# MCU.net
KiCad netlist of a schematic drawn in Altium Designer
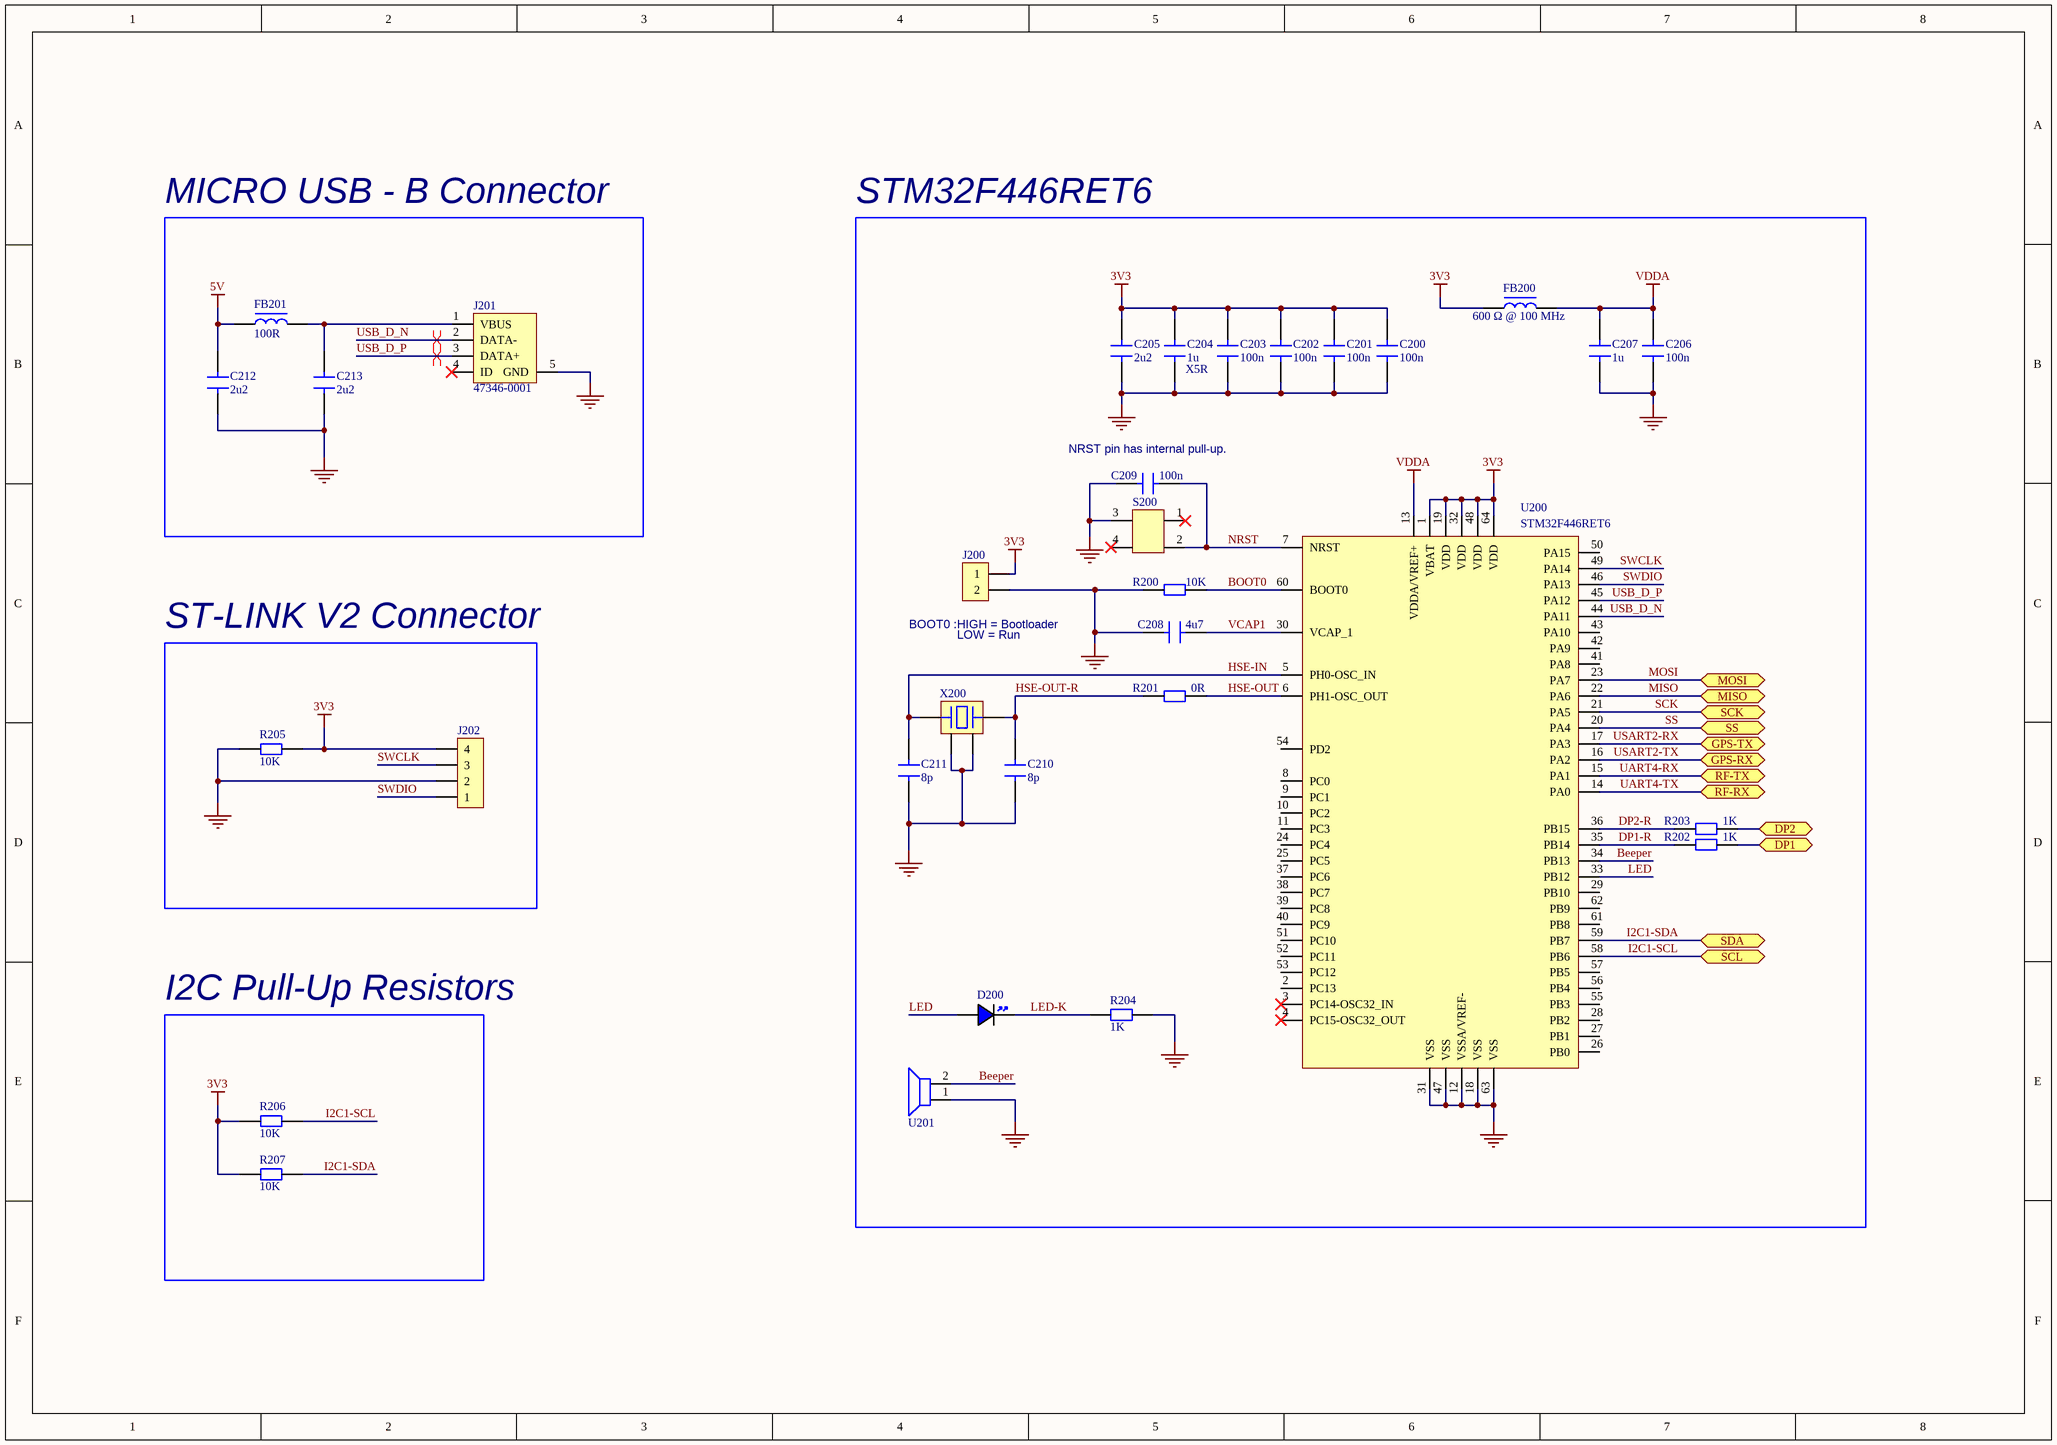
[diagram p0: MCU.SchDoc]

(export (version "E")
  (design (tool "Eeschema 10.0.6"))
  (components
    (comp (ref "C200")
      (value "100n")
      (footprint "CAP 0603")
      (description "Capacitor SMD 0603 50V")
      (libsource (lib "Schlib") (part "CAP 0603 50V"))
    )
    (comp (ref "C201")
      (value "100n")
      (footprint "CAP 0603")
      (description "Capacitor SMD 0603 50V")
      (libsource (lib "Schlib") (part "CAP 0603 50V"))
    )
    (comp (ref "C202")
      (value "100n")
      (footprint "CAP 0603")
      (description "Capacitor SMD 0603 50V")
      (libsource (lib "Schlib") (part "CAP 0603 50V"))
    )
    (comp (ref "C203")
      (value "100n")
      (footprint "CAP 0603")
      (description "Capacitor SMD 0603 50V")
      (libsource (lib "Schlib") (part "CAP 0603 50V"))
    )
    (comp (ref "C204")
      (value "1u")
      (footprint "CAP 0603")
      (description "Capacitor SMD 0603 16V")
      (libsource (lib "Schlib") (part "CAP 0603 16V"))
    )
    (comp (ref "C205")
      (value "2u2")
      (footprint "CAP 0603")
      (description "Capacitor SMD 0603 50V")
      (libsource (lib "Schlib") (part "CAP 0603 50V"))
    )
    (comp (ref "C206")
      (value "100n")
      (footprint "CAP 0603")
      (description "Capacitor SMD 0603 50V")
      (libsource (lib "Schlib") (part "CAP 0603 50V"))
    )
    (comp (ref "C207")
      (value "1u")
      (footprint "CAP 0603")
      (description "Capacitor SMD 0603 50V")
      (libsource (lib "Schlib") (part "CAP 0603 50V"))
    )
    (comp (ref "C208")
      (value "4u7")
      (footprint "CAP 0805")
      (description "Capacitor SMD 0805 25V")
      (libsource (lib "Schlib") (part "CAP 0805 25V"))
    )
    (comp (ref "C209")
      (value "100n")
      (footprint "CAP 0603")
      (description "Capacitor SMD 0603 50V")
      (libsource (lib "Schlib") (part "CAP 0603 50V"))
    )
    (comp (ref "C210")
      (value "8p")
      (footprint "CAP 0603")
      (description "Capacitor SMD 0603 50V")
      (libsource (lib "Schlib") (part "CAP 0603 50V"))
    )
    (comp (ref "C211")
      (value "8p")
      (footprint "CAP 0603")
      (description "Capacitor SMD 0603 50V")
      (libsource (lib "Schlib") (part "CAP 0603 50V"))
    )
    (comp (ref "C212")
      (value "2u2")
      (footprint "CAP 0603")
      (description "Capacitor SMD 0603 50V")
      (libsource (lib "Schlib") (part "CAP 0603 50V"))
    )
    (comp (ref "C213")
      (value "2u2")
      (footprint "CAP 0603")
      (description "Capacitor SMD 0603 50V")
      (libsource (lib "Schlib") (part "CAP 0603 50V"))
    )
    (comp (ref "D200")
      (value "LED 0805 BLUE")
      (footprint "LED 0805 BLUE")
      (description "LED 0805 GREEN SMD")
      (libsource (lib "Schlib") (part "LED 0805 BLUE"))
    )
    (comp (ref "FB200")
      (value "600 Ω @ 100 MHz")
      (footprint "FB 0603")
      (description "Ferrite Bead SMD 0603")
      (libsource (lib "Schlib") (part "FB 0603"))
    )
    (comp (ref "FB201")
      (value "100R")
      (footprint "FB 0805")
      (description "Ferrite Bead SMD 0805")
      (libsource (lib "Schlib") (part "FB 0805"))
    )
    (comp (ref "J200")
      (value "1x2 HEADER")
      (footprint "1x2 HEADER MALE")
      (libsource (lib "Schlib") (part "1x2 HEADER"))
    )
    (comp (ref "J201")
      (value "47346-0001")
      (footprint "MOLEX_47346-0001")
      (description "Micro-USB B Receptacle with Flange, Bottom Mount, Surface Mount, Lead-Free")
      (fields (field (name "MANUFACTURER") "Molex"))
      (libsource (lib "Schlib") (part "47346-0001"))
    )
    (comp (ref "J202")
      (value "1x4 HEADER MALE")
      (footprint "1X4 HEADER MALE")
      (libsource (lib "Schlib") (part "1x4 HEADER MALE"))
    )
    (comp (ref "R200")
      (value "10K")
      (footprint "RES 0603")
      (description "Resistor SMD 0603")
      (libsource (lib "Schlib") (part "RES 0603"))
    )
    (comp (ref "R201")
      (value "0R")
      (footprint "RES 0603")
      (description "Resistor SMD 0603")
      (libsource (lib "Schlib") (part "RES 0603"))
    )
    (comp (ref "R202")
      (value "1K")
      (footprint "RES 0603")
      (description "Resistor SMD 0603")
      (libsource (lib "Schlib") (part "RES 0603"))
    )
    (comp (ref "R203")
      (value "1K")
      (footprint "RES 0603")
      (description "Resistor SMD 0603")
      (libsource (lib "Schlib") (part "RES 0603"))
    )
    (comp (ref "R204")
      (value "1K")
      (footprint "RES 0603")
      (description "Resistor SMD 0603")
      (libsource (lib "Schlib") (part "RES 0603"))
    )
    (comp (ref "R205")
      (value "10K")
      (footprint "RES 0603")
      (description "Resistor SMD 0603")
      (libsource (lib "Schlib") (part "RES 0603"))
    )
    (comp (ref "R206")
      (value "10K")
      (footprint "RES 0603")
      (description "Resistor SMD 0603")
      (libsource (lib "Schlib") (part "RES 0603"))
    )
    (comp (ref "R207")
      (value "10K")
      (footprint "RES 0603")
      (description "Resistor SMD 0603")
      (libsource (lib "Schlib") (part "RES 0603"))
    )
    (comp (ref "S200")
      (value "FSM4JSMATR")
      (footprint "FSM4JSMATR")
      (description "Switch Tactile OFF (ON) SPST Round Button Gull Wing 0.05A 24VDC 1.57N SMD T/R")
      (fields (field (name "MANUFACTURER") "TE Connectivity Alcoswitch"))
      (libsource (lib "Schlib") (part "FSM4JSMATR"))
    )
    (comp (ref "U200")
      (value "STM32F446RET6")
      (footprint "STM32F446RET6")
      (description "ARM® Cortex®-M4 STM32 F4 Microcontroller IC 32-Bit 180MHz 512KB (512K x 8) FLASH 64-LQFP (10x10)")
      (fields (field (name "MANUFACTURER") "STMicroelectronics"))
      (libsource (lib "Schlib") (part "STM32F446RET6"))
    )
    (comp (ref "U201")
      (value "PS1240P02BT")
      (footprint "PS1240P02BT")
      (description "Audio Buzzer Piezo 30Vo-p 3Vo-p 70dBA Through Hole Pin Ammo")
      (fields (field (name "MANUFACTURER") "TDK"))
      (libsource (lib "Schlib") (part "PS1240P02BT"))
    )
    (comp (ref "X200")
      (value "FA-20H 16.0000MF10Z-AJ0")
      (footprint "FA-20H 16.0000MF10Z-AJ0")
      (description "Crystal 16MHz ±10ppm (Tol) ±10ppm (Stability) 8pF FUND 80Ohm 4-Pin Ultra Mini-CSMD T/R")
      (fields (field (name "MANUFACTURER") "Epson"))
      (libsource (lib "Schlib") (part "FA-20H 16.0000MF10Z-AJ0"))
    )
  )
  (nets
    (net (code "1") (name "/BOOT0") (class "Default")
      (node (ref "R200") (pin "2") (pinfunction "2_2") (pintype "passive"))
      (node (ref "U200") (pin "60") (pinfunction "BOOT0_60") (pintype "passive"))
    )
    (net (code "2") (name "/Beeper") (class "Default")
      (node (ref "U200") (pin "34") (pinfunction "PB13_34") (pintype "passive"))
      (node (ref "U201") (pin "2") (pinfunction "2_2") (pintype "passive"))
    )
    (net (code "3") (name "/DP1") (class "Default")
      (node (ref "R202") (pin "1") (pinfunction "1_1") (pintype "passive"))
    )
    (net (code "4") (name "/DP1-R") (class "Default")
      (node (ref "R202") (pin "2") (pinfunction "2_2") (pintype "passive"))
      (node (ref "U200") (pin "35") (pinfunction "PB14_35") (pintype "passive"))
    )
    (net (code "5") (name "/DP2") (class "Default")
      (node (ref "R203") (pin "2") (pinfunction "2_2") (pintype "passive"))
    )
    (net (code "6") (name "/DP2-R") (class "Default")
      (node (ref "R203") (pin "1") (pinfunction "1_1") (pintype "passive"))
      (node (ref "U200") (pin "36") (pinfunction "PB15_36") (pintype "passive"))
    )
    (net (code "7") (name "/HSE-IN") (class "Default")
      (node (ref "C211") (pin "2") (pinfunction "2_2") (pintype "passive"))
      (node (ref "U200") (pin "5") (pinfunction "PH0-OSC_IN_5") (pintype "passive"))
      (node (ref "X200") (pin "1") (pinfunction "1_1") (pintype "passive"))
    )
    (net (code "8") (name "/HSE-OUT") (class "Default")
      (node (ref "R201") (pin "2") (pinfunction "2_2") (pintype "passive"))
      (node (ref "U200") (pin "6") (pinfunction "PH1-OSC_OUT_6") (pintype "passive"))
    )
    (net (code "9") (name "/HSE-OUT-R") (class "Default")
      (node (ref "C210") (pin "2") (pinfunction "2_2") (pintype "passive"))
      (node (ref "R201") (pin "1") (pinfunction "1_1") (pintype "passive"))
      (node (ref "X200") (pin "3") (pinfunction "3_3") (pintype "passive"))
    )
    (net (code "10") (name "/I2C1-SCL") (class "Default")
      (node (ref "R206") (pin "1") (pinfunction "1_1") (pintype "passive"))
      (node (ref "U200") (pin "58") (pinfunction "PB6_58") (pintype "passive"))
    )
    (net (code "11") (name "/I2C1-SDA") (class "Default")
      (node (ref "R207") (pin "1") (pinfunction "1_1") (pintype "passive"))
      (node (ref "U200") (pin "59") (pinfunction "PB7_59") (pintype "passive"))
    )
    (net (code "12") (name "/LED") (class "Default")
      (node (ref "D200") (pin "A") (pinfunction "A_A") (pintype "passive"))
      (node (ref "U200") (pin "33") (pinfunction "PB12_33") (pintype "passive"))
    )
    (net (code "13") (name "/LED-K") (class "Default")
      (node (ref "D200") (pin "K") (pinfunction "K_K") (pintype "passive"))
      (node (ref "R204") (pin "1") (pinfunction "1_1") (pintype "passive"))
    )
    (net (code "14") (name "/MISO") (class "Default")
      (node (ref "U200") (pin "22") (pinfunction "PA6_22") (pintype "passive"))
    )
    (net (code "15") (name "/MOSI") (class "Default")
      (node (ref "U200") (pin "23") (pinfunction "PA7_23") (pintype "passive"))
    )
    (net (code "16") (name "/NRST") (class "Default")
      (node (ref "C209") (pin "2") (pinfunction "2_2") (pintype "passive"))
      (node (ref "S200") (pin "2") (pinfunction "2_2") (pintype "passive"))
      (node (ref "U200") (pin "7") (pinfunction "NRST_7") (pintype "passive"))
    )
    (net (code "17") (name "/SCK") (class "Default")
      (node (ref "U200") (pin "21") (pinfunction "PA5_21") (pintype "passive"))
    )
    (net (code "18") (name "/SS") (class "Default")
      (node (ref "U200") (pin "20") (pinfunction "PA4_20") (pintype "passive"))
    )
    (net (code "19") (name "/SWCLK") (class "Default")
      (node (ref "J202") (pin "3") (pinfunction "3_3") (pintype "passive"))
      (node (ref "U200") (pin "49") (pinfunction "PA14_49") (pintype "passive"))
    )
    (net (code "20") (name "/SWDIO") (class "Default")
      (node (ref "J202") (pin "1") (pinfunction "1_1") (pintype "passive"))
      (node (ref "U200") (pin "46") (pinfunction "PA13_46") (pintype "passive"))
    )
    (net (code "21") (name "/UART4-RX") (class "Default")
      (node (ref "U200") (pin "15") (pinfunction "PA1_15") (pintype "passive"))
    )
    (net (code "22") (name "/UART4-TX") (class "Default")
      (node (ref "U200") (pin "14") (pinfunction "PA0_14") (pintype "passive"))
    )
    (net (code "23") (name "/USART2-RX") (class "Default")
      (node (ref "U200") (pin "17") (pinfunction "PA3_17") (pintype "passive"))
    )
    (net (code "24") (name "/USART2-TX") (class "Default")
      (node (ref "U200") (pin "16") (pinfunction "PA2_16") (pintype "passive"))
    )
    (net (code "25") (name "/USB_D_N") (class "Default")
      (node (ref "J201") (pin "2") (pinfunction "DATA-_2") (pintype "passive"))
      (node (ref "U200") (pin "44") (pinfunction "PA11_44") (pintype "passive"))
    )
    (net (code "26") (name "/USB_D_P") (class "Default")
      (node (ref "J201") (pin "3") (pinfunction "DATA+_3") (pintype "passive"))
      (node (ref "U200") (pin "45") (pinfunction "PA12_45") (pintype "passive"))
    )
    (net (code "27") (name "/VCAP1") (class "Default")
      (node (ref "C208") (pin "2") (pinfunction "2_2") (pintype "passive"))
      (node (ref "U200") (pin "30") (pinfunction "VCAP_1_30") (pintype "passive"))
    )
    (net (code "28") (name "3V3") (class "Default")
      (node (ref "C200") (pin "2") (pinfunction "2_2") (pintype "passive"))
      (node (ref "C201") (pin "2") (pinfunction "2_2") (pintype "passive"))
      (node (ref "C202") (pin "2") (pinfunction "2_2") (pintype "passive"))
      (node (ref "C203") (pin "2") (pinfunction "2_2") (pintype "passive"))
      (node (ref "C204") (pin "2") (pinfunction "2_2") (pintype "passive"))
      (node (ref "C205") (pin "2") (pinfunction "2_2") (pintype "passive"))
      (node (ref "FB200") (pin "1") (pintype "passive"))
      (node (ref "J200") (pin "1") (pinfunction "1_1") (pintype "passive"))
      (node (ref "J202") (pin "4") (pinfunction "4_4") (pintype "passive"))
      (node (ref "R205") (pin "2") (pinfunction "2_2") (pintype "passive"))
      (node (ref "R206") (pin "2") (pinfunction "2_2") (pintype "passive"))
      (node (ref "R207") (pin "2") (pinfunction "2_2") (pintype "passive"))
      (node (ref "U200") (pin "1") (pinfunction "VBAT_1") (pintype "passive"))
      (node (ref "U200") (pin "19") (pinfunction "VDD_19") (pintype "passive"))
      (node (ref "U200") (pin "32") (pinfunction "VDD_32") (pintype "passive"))
      (node (ref "U200") (pin "48") (pinfunction "VDD_48") (pintype "passive"))
      (node (ref "U200") (pin "64") (pinfunction "VDD_64") (pintype "passive"))
    )
    (net (code "29") (name "5V") (class "Default")
      (node (ref "C212") (pin "1") (pinfunction "1_1") (pintype "passive"))
      (node (ref "FB201") (pin "1") (pintype "passive"))
    )
    (net (code "30") (name "GND") (class "Default")
      (node (ref "C200") (pin "1") (pinfunction "1_1") (pintype "passive"))
      (node (ref "C201") (pin "1") (pinfunction "1_1") (pintype "passive"))
      (node (ref "C202") (pin "1") (pinfunction "1_1") (pintype "passive"))
      (node (ref "C203") (pin "1") (pinfunction "1_1") (pintype "passive"))
      (node (ref "C204") (pin "1") (pinfunction "1_1") (pintype "passive"))
      (node (ref "C205") (pin "1") (pinfunction "1_1") (pintype "passive"))
      (node (ref "C206") (pin "1") (pinfunction "1_1") (pintype "passive"))
      (node (ref "C207") (pin "1") (pinfunction "1_1") (pintype "passive"))
      (node (ref "C208") (pin "1") (pinfunction "1_1") (pintype "passive"))
      (node (ref "C209") (pin "1") (pinfunction "1_1") (pintype "passive"))
      (node (ref "C210") (pin "1") (pinfunction "1_1") (pintype "passive"))
      (node (ref "C211") (pin "1") (pinfunction "1_1") (pintype "passive"))
      (node (ref "C212") (pin "2") (pinfunction "2_2") (pintype "passive"))
      (node (ref "C213") (pin "2") (pinfunction "2_2") (pintype "passive"))
      (node (ref "J200") (pin "2") (pinfunction "2_2") (pintype "passive"))
      (node (ref "J201") (pin "5") (pinfunction "GND_5") (pintype "passive"))
      (node (ref "J202") (pin "2") (pinfunction "2_2") (pintype "passive"))
      (node (ref "R200") (pin "1") (pinfunction "1_1") (pintype "passive"))
      (node (ref "R204") (pin "2") (pinfunction "2_2") (pintype "passive"))
      (node (ref "R205") (pin "1") (pinfunction "1_1") (pintype "passive"))
      (node (ref "S200") (pin "3") (pinfunction "3_3") (pintype "passive"))
      (node (ref "U200") (pin "12") (pinfunction "VSSA/VREF-_12") (pintype "passive"))
      (node (ref "U200") (pin "18") (pinfunction "VSS_18") (pintype "passive"))
      (node (ref "U200") (pin "31") (pinfunction "VSS_31") (pintype "passive"))
      (node (ref "U200") (pin "47") (pinfunction "VSS_47") (pintype "passive"))
      (node (ref "U200") (pin "63") (pinfunction "VSS_63") (pintype "passive"))
      (node (ref "U201") (pin "1") (pinfunction "1_1") (pintype "passive"))
      (node (ref "X200") (pin "2") (pinfunction "2_2") (pintype "passive"))
      (node (ref "X200") (pin "4") (pinfunction "4_4") (pintype "passive"))
    )
    (net (code "31") (name "Net-(J201-VBUS)") (class "Default")
      (node (ref "C213") (pin "1") (pinfunction "1_1") (pintype "passive"))
      (node (ref "FB201") (pin "2") (pintype "passive"))
      (node (ref "J201") (pin "1") (pinfunction "VBUS_1") (pintype "passive"))
    )
    (net (code "32") (name "VDDA") (class "Default")
      (node (ref "C206") (pin "2") (pinfunction "2_2") (pintype "passive"))
      (node (ref "C207") (pin "2") (pinfunction "2_2") (pintype "passive"))
      (node (ref "FB200") (pin "2") (pintype "passive"))
      (node (ref "U200") (pin "13") (pinfunction "VDDA/VREF+_13") (pintype "passive"))
    )
    (net (code "33") (name "unconnected-(J201-ID-Pad4)") (class "Default")
      (node (ref "J201") (pin "4") (pinfunction "ID_4") (pintype "passive+no_connect"))
    )
    (net (code "34") (name "unconnected-(S200-Pad1)") (class "Default")
      (node (ref "S200") (pin "1") (pinfunction "1_1") (pintype "passive+no_connect"))
    )
    (net (code "35") (name "unconnected-(S200-Pad4)") (class "Default")
      (node (ref "S200") (pin "4") (pinfunction "4_4") (pintype "passive+no_connect"))
    )
    (net (code "36") (name "unconnected-(U200-PA8-Pad41)") (class "Default")
      (node (ref "U200") (pin "41") (pinfunction "PA8_41") (pintype "passive"))
    )
    (net (code "37") (name "unconnected-(U200-PA9-Pad42)") (class "Default")
      (node (ref "U200") (pin "42") (pinfunction "PA9_42") (pintype "passive"))
    )
    (net (code "38") (name "unconnected-(U200-PA10-Pad43)") (class "Default")
      (node (ref "U200") (pin "43") (pinfunction "PA10_43") (pintype "passive"))
    )
    (net (code "39") (name "unconnected-(U200-PA15-Pad50)") (class "Default")
      (node (ref "U200") (pin "50") (pinfunction "PA15_50") (pintype "passive"))
    )
    (net (code "40") (name "unconnected-(U200-PB0-Pad26)") (class "Default")
      (node (ref "U200") (pin "26") (pinfunction "PB0_26") (pintype "passive"))
    )
    (net (code "41") (name "unconnected-(U200-PB1-Pad27)") (class "Default")
      (node (ref "U200") (pin "27") (pinfunction "PB1_27") (pintype "passive"))
    )
    (net (code "42") (name "unconnected-(U200-PB2-Pad28)") (class "Default")
      (node (ref "U200") (pin "28") (pinfunction "PB2_28") (pintype "passive"))
    )
    (net (code "43") (name "unconnected-(U200-PB3-Pad55)") (class "Default")
      (node (ref "U200") (pin "55") (pinfunction "PB3_55") (pintype "passive"))
    )
    (net (code "44") (name "unconnected-(U200-PB4-Pad56)") (class "Default")
      (node (ref "U200") (pin "56") (pinfunction "PB4_56") (pintype "passive"))
    )
    (net (code "45") (name "unconnected-(U200-PB5-Pad57)") (class "Default")
      (node (ref "U200") (pin "57") (pinfunction "PB5_57") (pintype "passive"))
    )
    (net (code "46") (name "unconnected-(U200-PB8-Pad61)") (class "Default")
      (node (ref "U200") (pin "61") (pinfunction "PB8_61") (pintype "passive"))
    )
    (net (code "47") (name "unconnected-(U200-PB9-Pad62)") (class "Default")
      (node (ref "U200") (pin "62") (pinfunction "PB9_62") (pintype "passive"))
    )
    (net (code "48") (name "unconnected-(U200-PB10-Pad29)") (class "Default")
      (node (ref "U200") (pin "29") (pinfunction "PB10_29") (pintype "passive"))
    )
    (net (code "49") (name "unconnected-(U200-PC0-Pad8)") (class "Default")
      (node (ref "U200") (pin "8") (pinfunction "PC0_8") (pintype "passive"))
    )
    (net (code "50") (name "unconnected-(U200-PC1-Pad9)") (class "Default")
      (node (ref "U200") (pin "9") (pinfunction "PC1_9") (pintype "passive"))
    )
    (net (code "51") (name "unconnected-(U200-PC2-Pad10)") (class "Default")
      (node (ref "U200") (pin "10") (pinfunction "PC2_10") (pintype "passive"))
    )
    (net (code "52") (name "unconnected-(U200-PC3-Pad11)") (class "Default")
      (node (ref "U200") (pin "11") (pinfunction "PC3_11") (pintype "passive"))
    )
    (net (code "53") (name "unconnected-(U200-PC4-Pad24)") (class "Default")
      (node (ref "U200") (pin "24") (pinfunction "PC4_24") (pintype "passive"))
    )
    (net (code "54") (name "unconnected-(U200-PC5-Pad25)") (class "Default")
      (node (ref "U200") (pin "25") (pinfunction "PC5_25") (pintype "passive"))
    )
    (net (code "55") (name "unconnected-(U200-PC6-Pad37)") (class "Default")
      (node (ref "U200") (pin "37") (pinfunction "PC6_37") (pintype "passive"))
    )
    (net (code "56") (name "unconnected-(U200-PC7-Pad38)") (class "Default")
      (node (ref "U200") (pin "38") (pinfunction "PC7_38") (pintype "passive"))
    )
    (net (code "57") (name "unconnected-(U200-PC8-Pad39)") (class "Default")
      (node (ref "U200") (pin "39") (pinfunction "PC8_39") (pintype "passive"))
    )
    (net (code "58") (name "unconnected-(U200-PC9-Pad40)") (class "Default")
      (node (ref "U200") (pin "40") (pinfunction "PC9_40") (pintype "passive"))
    )
    (net (code "59") (name "unconnected-(U200-PC10-Pad51)") (class "Default")
      (node (ref "U200") (pin "51") (pinfunction "PC10_51") (pintype "passive"))
    )
    (net (code "60") (name "unconnected-(U200-PC11-Pad52)") (class "Default")
      (node (ref "U200") (pin "52") (pinfunction "PC11_52") (pintype "passive"))
    )
    (net (code "61") (name "unconnected-(U200-PC12-Pad53)") (class "Default")
      (node (ref "U200") (pin "53") (pinfunction "PC12_53") (pintype "passive"))
    )
    (net (code "62") (name "unconnected-(U200-PC13-Pad2)") (class "Default")
      (node (ref "U200") (pin "2") (pinfunction "PC13_2") (pintype "passive"))
    )
    (net (code "63") (name "unconnected-(U200-PC14-OSC32_IN-Pad3)") (class "Default")
      (node (ref "U200") (pin "3") (pinfunction "PC14-OSC32_IN_3") (pintype "passive+no_connect"))
    )
    (net (code "64") (name "unconnected-(U200-PC15-OSC32_OUT-Pad4)") (class "Default")
      (node (ref "U200") (pin "4") (pinfunction "PC15-OSC32_OUT_4") (pintype "passive+no_connect"))
    )
    (net (code "65") (name "unconnected-(U200-PD2-Pad54)") (class "Default")
      (node (ref "U200") (pin "54") (pinfunction "PD2_54") (pintype "passive"))
    )
  )
)
